# SpindlePidLcdStandAlone.net
KiCad netlist of a schematic drawn in EAGLE
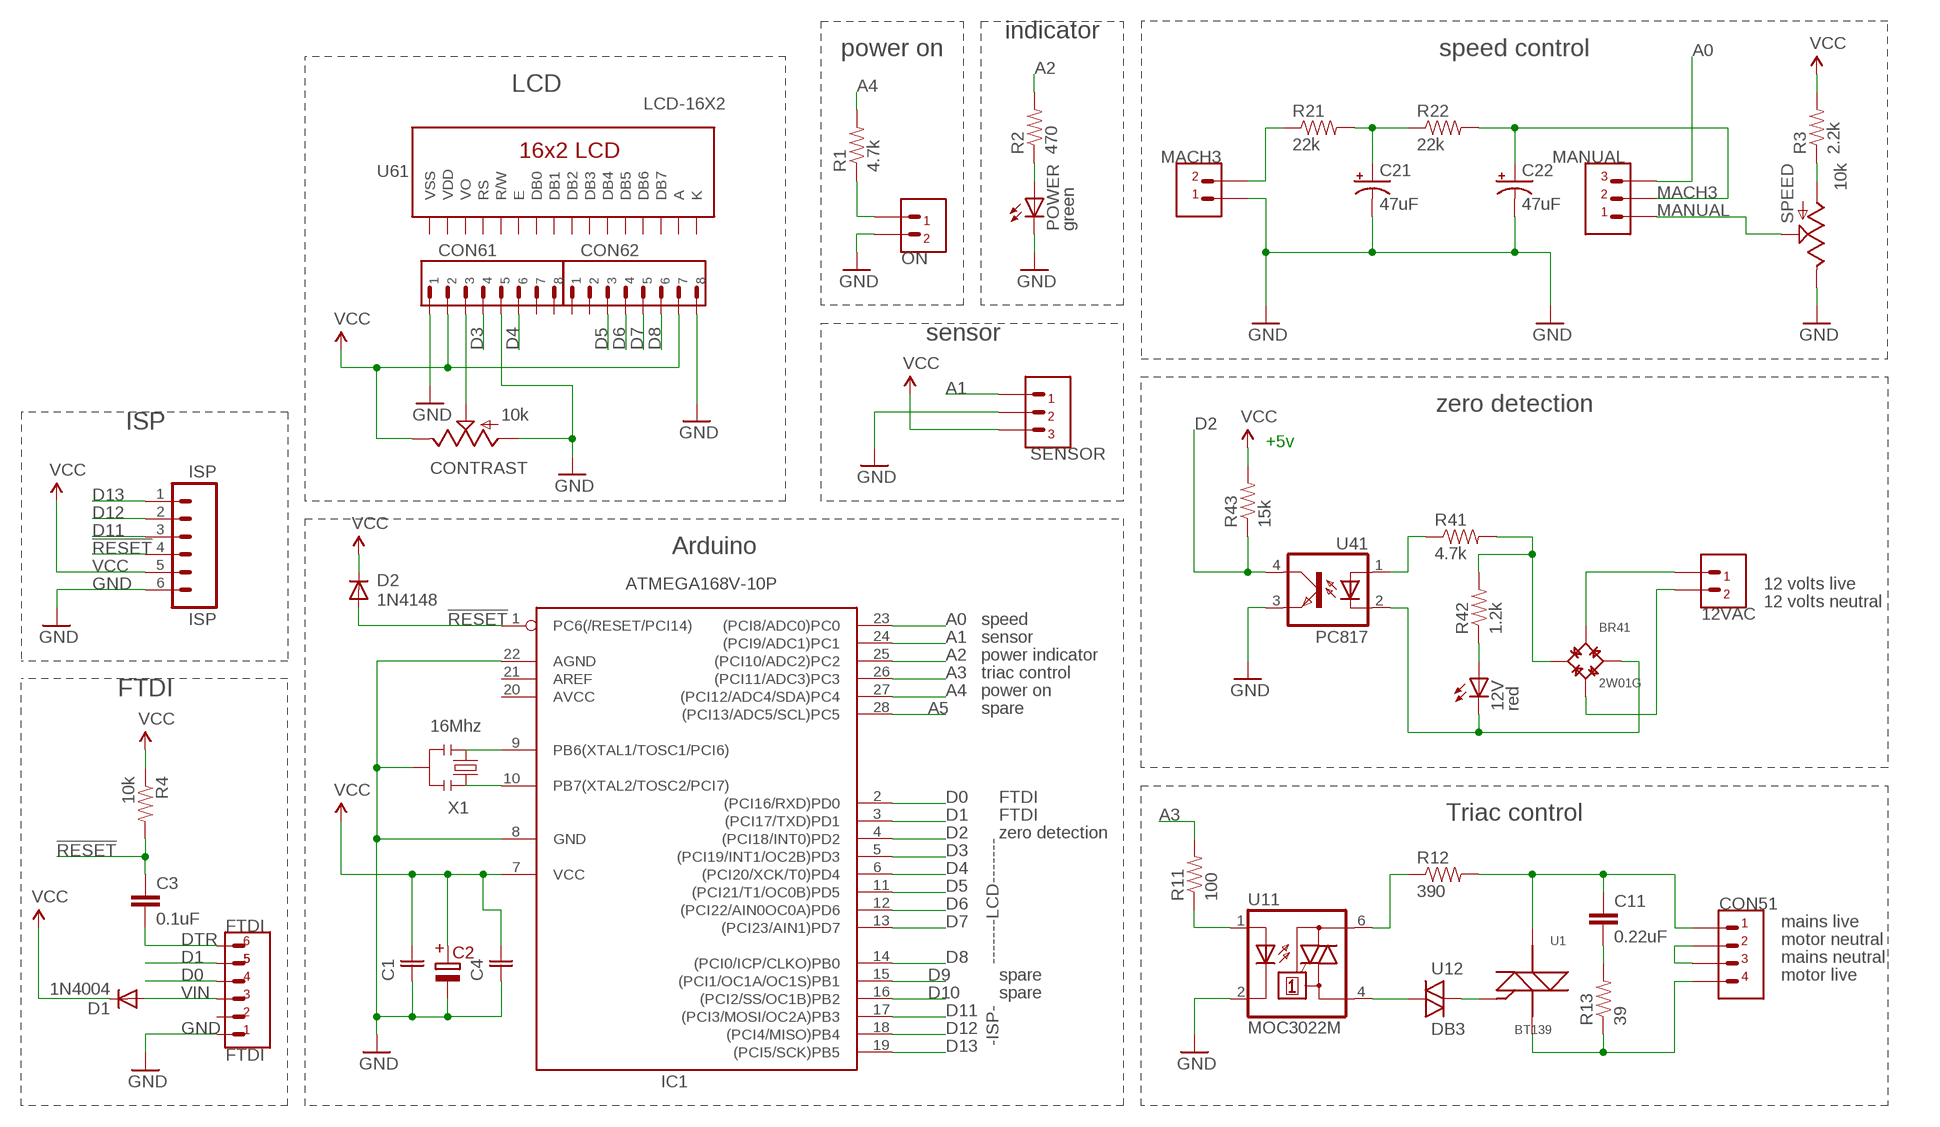
[diagram p0: schematic, sheet 1]

(export (version "E")
  (design (tool "Eeschema 10.0.6"))
  (components
    (comp (ref "12V")
      (value "red")
      (footprint "eagle-import:LED5MM")
      (libsource (lib "eagle-import") (part "LED5MM"))
    )
    (comp (ref "12VAC")
      (value "2PIN")
      (footprint "eagle-import:2PIN")
      (libsource (lib "eagle-import") (part "2PIN"))
    )
    (comp (ref "BR41")
      (value "2W01G")
      (footprint "eagle-import:DIODEBRIDGE")
      (libsource (lib "eagle-import") (part "DIODEBRIDGE"))
    )
    (comp (ref "C1")
      (value "0.1UF")
      (footprint "eagle-import:0.1UF")
      (libsource (lib "eagle-import") (part "0.1UF"))
    )
    (comp (ref "C2")
      (value "CAPACITOR")
      (footprint "eagle-import:CAPACITOR")
      (libsource (lib "eagle-import") (part "CAPACITOR"))
    )
    (comp (ref "C3")
      (value "0.1uF")
      (footprint "eagle-import:CAP-PTH-SMALL")
      (libsource (lib "eagle-import") (part "CAPPTH"))
    )
    (comp (ref "C4")
      (value "0.1UF")
      (footprint "eagle-import:0.1UF")
      (libsource (lib "eagle-import") (part "0.1UF"))
    )
    (comp (ref "C11")
      (value "0.22uF")
      (footprint "eagle-import:CAP-PTH-SMALL")
      (libsource (lib "eagle-import") (part "CAPPTH"))
    )
    (comp (ref "C21")
      (value "47uF")
      (footprint "eagle-import:CPOL-RADIAL-10UF-25V")
      (libsource (lib "eagle-import") (part "CAP_POLPTH2"))
    )
    (comp (ref "C22")
      (value "47uF")
      (footprint "eagle-import:CPOL-RADIAL-10UF-25V")
      (libsource (lib "eagle-import") (part "CAP_POLPTH2"))
    )
    (comp (ref "CON51")
      (value "4PIN")
      (footprint "eagle-import:4PIN")
      (libsource (lib "eagle-import") (part "4PIN"))
    )
    (comp (ref "CON61")
      (value "8PINHEADER")
      (footprint "eagle-import:8PINHEADER")
      (libsource (lib "eagle-import") (part "8PINHEADER"))
    )
    (comp (ref "CON62")
      (value "8PINHEADER")
      (footprint "eagle-import:8PINHEADER")
      (libsource (lib "eagle-import") (part "8PINHEADER"))
    )
    (comp (ref "CONTRAST")
      (value "10k")
      (footprint "eagle-import:ALPS_POT")
      (libsource (lib "eagle-import") (part "POT"))
    )
    (comp (ref "D1")
      (value "1N4004")
      (footprint "eagle-import:DO41-10")
      (libsource (lib "eagle-import") (part "1N4004"))
    )
    (comp (ref "D2")
      (value "1N4148")
      (footprint "eagle-import:DO41-10")
      (libsource (lib "eagle-import") (part "1N4004"))
    )
    (comp (ref "FTDI")
      (value "FTDI")
      (footprint "eagle-import:6PINHEADER")
      (libsource (lib "eagle-import") (part "6PINHEADER0.1{dblquote}"))
    )
    (comp (ref "IC1")
      (value "ATMEGA168V-10P")
      (footprint "eagle-import:DIL28-3")
      (libsource (lib "eagle-import") (part "ATMEGA168PV-10"))
    )
    (comp (ref "ISP")
      (value "ISP")
      (footprint "eagle-import:1X06")
      (libsource (lib "eagle-import") (part "M06SIP"))
    )
    (comp (ref "MACH3")
      (value "2PIN")
      (footprint "eagle-import:2PIN")
      (libsource (lib "eagle-import") (part "2PIN"))
    )
    (comp (ref "MANUAL")
      (value "3PIN")
      (footprint "eagle-import:3PIN")
      (libsource (lib "eagle-import") (part "3PIN"))
    )
    (comp (ref "ON")
      (value "2PIN")
      (footprint "eagle-import:2PIN")
      (libsource (lib "eagle-import") (part "2PIN"))
    )
    (comp (ref "POWER")
      (value "green")
      (footprint "eagle-import:LED5MM")
      (libsource (lib "eagle-import") (part "LED5MM"))
    )
    (comp (ref "R1")
      (value "4.7k")
      (footprint "eagle-import:AXIAL-0.4")
      (libsource (lib "eagle-import") (part "RESISTORPTH-1/4W"))
    )
    (comp (ref "R2")
      (value "470")
      (footprint "eagle-import:1_6W-RES")
      (libsource (lib "eagle-import") (part "RESISTORPTH-1/6W"))
    )
    (comp (ref "R3")
      (value "2.2k")
      (footprint "eagle-import:1_6W-RES")
      (libsource (lib "eagle-import") (part "RESISTORPTH-1/6W"))
    )
    (comp (ref "R4")
      (value "10k")
      (footprint "eagle-import:AXIAL-0.4")
      (libsource (lib "eagle-import") (part "RESISTORPTH-1/4W"))
    )
    (comp (ref "R11")
      (value "100")
      (footprint "eagle-import:1_6W-RES")
      (libsource (lib "eagle-import") (part "RESISTORPTH-1/6W"))
    )
    (comp (ref "R12")
      (value "390")
      (footprint "eagle-import:1_6W-RES")
      (libsource (lib "eagle-import") (part "RESISTORPTH-1/6W"))
    )
    (comp (ref "R13")
      (value "39")
      (footprint "eagle-import:1_6W-RES")
      (libsource (lib "eagle-import") (part "RESISTORPTH-1/6W"))
    )
    (comp (ref "R21")
      (value "22k")
      (footprint "eagle-import:1_6W-RES")
      (libsource (lib "eagle-import") (part "RESISTORPTH-1/6W"))
    )
    (comp (ref "R22")
      (value "22k")
      (footprint "eagle-import:1_6W-RES")
      (libsource (lib "eagle-import") (part "RESISTORPTH-1/6W"))
    )
    (comp (ref "R41")
      (value "4.7k")
      (footprint "eagle-import:1_6W-RES")
      (libsource (lib "eagle-import") (part "RESISTORPTH-1/6W"))
    )
    (comp (ref "R42")
      (value "1.2k")
      (footprint "eagle-import:1_6W-RES")
      (libsource (lib "eagle-import") (part "RESISTORPTH-1/6W"))
    )
    (comp (ref "R43")
      (value "15k")
      (footprint "eagle-import:1_6W-RES")
      (libsource (lib "eagle-import") (part "RESISTORPTH-1/6W"))
    )
    (comp (ref "SENSOR")
      (value "3PIN")
      (footprint "eagle-import:3PIN")
      (libsource (lib "eagle-import") (part "3PIN"))
    )
    (comp (ref "SPEED")
      (value "10k")
      (footprint "eagle-import:ALPS_POT")
      (libsource (lib "eagle-import") (part "POT"))
    )
    (comp (ref "U1")
      (value "BT139")
      (footprint "eagle-import:TRIAC")
      (libsource (lib "eagle-import") (part "TRIAC"))
    )
    (comp (ref "U11")
      (value "MOC3022M")
      (footprint "eagle-import:DIL06")
      (fields (field (name "MF") "FAIRCHILD SEMICONDUCTOR") (field (name "MPN") "MOC3022-M"))
      (libsource (lib "eagle-import") (part "MOC30M22"))
    )
    (comp (ref "U12")
      (value "DB3")
      (footprint "eagle-import:DO35-10")
      (libsource (lib "eagle-import") (part "DIAC-DO35-10"))
    )
    (comp (ref "U41")
      (value "PC817")
      (footprint "eagle-import:DIL04")
      (fields (field (name "MPN") "PC817X4J000F"))
      (libsource (lib "eagle-import") (part "PC817"))
    )
    (comp (ref "U61")
      (value "LCD-16X2")
      (footprint "eagle-import:LCD-16X2")
      (libsource (lib "eagle-import") (part "LCD-16X2SILK"))
    )
    (comp (ref "X1")
      (value "16Mhz")
      (footprint "eagle-import:RESONATOR-PTH")
      (libsource (lib "eagle-import") (part "RESONATORPTH"))
    )
  )
  (nets
    (net (code "1") (name "/A") (class "Default")
      (node (ref "U61") (pin "15") (pinfunction "A_15") (pintype "power_in"))
    )
    (net (code "2") (name "/A0") (class "Default")
      (node (ref "IC1") (pin "23") (pinfunction "(PCI8/ADC0)PC0_23") (pintype "bidirectional"))
      (node (ref "MANUAL") (pin "P$3") (pinfunction "3_P$3") (pintype "bidirectional"))
    )
    (net (code "3") (name "/A1") (class "Default")
      (node (ref "IC1") (pin "24") (pinfunction "(PCI9/ADC1)PC1_24") (pintype "bidirectional"))
      (node (ref "SENSOR") (pin "P$1") (pinfunction "1_P$1") (pintype "bidirectional"))
    )
    (net (code "4") (name "/A2") (class "Default")
      (node (ref "IC1") (pin "25") (pinfunction "(PCI10/ADC2)PC2_25") (pintype "bidirectional"))
      (node (ref "R2") (pin "2") (pinfunction "2_2") (pintype "passive"))
    )
    (net (code "5") (name "/A3") (class "Default")
      (node (ref "IC1") (pin "26") (pinfunction "(PCI11/ADC3)PC3_26") (pintype "bidirectional"))
      (node (ref "R11") (pin "2") (pinfunction "2_2") (pintype "passive"))
    )
    (net (code "6") (name "/A4") (class "Default")
      (node (ref "IC1") (pin "27") (pinfunction "(PCI12/ADC4/SDA)PC4_27") (pintype "bidirectional"))
      (node (ref "R1") (pin "P$2") (pinfunction "2_P$2") (pintype "passive"))
    )
    (net (code "7") (name "/A5") (class "Default")
      (node (ref "IC1") (pin "28") (pinfunction "(PCI13/ADC5/SCL)PC5_28") (pintype "bidirectional"))
    )
    (net (code "8") (name "/D0") (class "Default")
      (node (ref "FTDI") (pin "P$4") (pinfunction "P$4_P$4") (pintype "bidirectional"))
      (node (ref "IC1") (pin "2") (pinfunction "(PCI16/RXD)PD0_2") (pintype "bidirectional"))
    )
    (net (code "9") (name "/D1") (class "Default")
      (node (ref "FTDI") (pin "P$5") (pinfunction "P$5_P$5") (pintype "bidirectional"))
      (node (ref "IC1") (pin "3") (pinfunction "(PCI17/TXD)PD1_3") (pintype "bidirectional"))
    )
    (net (code "10") (name "/D2") (class "Default")
      (node (ref "IC1") (pin "4") (pinfunction "(PCI18/INT0)PD2_4") (pintype "bidirectional"))
      (node (ref "R43") (pin "1") (pinfunction "1_1") (pintype "passive"))
      (node (ref "U41") (pin "4") (pinfunction "COL_4") (pintype "passive"))
    )
    (net (code "11") (name "/D3") (class "Default")
      (node (ref "CON61") (pin "P$4") (pinfunction "P$4_P$4") (pintype "bidirectional"))
      (node (ref "IC1") (pin "5") (pinfunction "(PCI19/INT1/OC2B)PD3_5") (pintype "bidirectional"))
    )
    (net (code "12") (name "/D4") (class "Default")
      (node (ref "CON61") (pin "P$6") (pinfunction "P$6_P$6") (pintype "bidirectional"))
      (node (ref "IC1") (pin "6") (pinfunction "(PCI20/XCK/T0)PD4_6") (pintype "bidirectional"))
    )
    (net (code "13") (name "/D5") (class "Default")
      (node (ref "CON62") (pin "P$3") (pinfunction "P$3_P$3") (pintype "bidirectional"))
      (node (ref "IC1") (pin "11") (pinfunction "(PCI21/T1/OC0B)PD5_11") (pintype "bidirectional"))
    )
    (net (code "14") (name "/D6") (class "Default")
      (node (ref "CON62") (pin "P$4") (pinfunction "P$4_P$4") (pintype "bidirectional"))
      (node (ref "IC1") (pin "12") (pinfunction "(PCI22/AIN0OC0A)PD6_12") (pintype "bidirectional"))
    )
    (net (code "15") (name "/D7") (class "Default")
      (node (ref "CON62") (pin "P$5") (pinfunction "P$5_P$5") (pintype "bidirectional"))
      (node (ref "IC1") (pin "13") (pinfunction "(PCI23/AIN1)PD7_13") (pintype "bidirectional"))
    )
    (net (code "16") (name "/D8") (class "Default")
      (node (ref "CON62") (pin "P$6") (pinfunction "P$6_P$6") (pintype "bidirectional"))
      (node (ref "IC1") (pin "14") (pinfunction "(PCI0/ICP/CLKO)PB0_14") (pintype "bidirectional"))
    )
    (net (code "17") (name "/D9") (class "Default")
      (node (ref "IC1") (pin "15") (pinfunction "(PCI1/OC1A/OC1S)PB1_15") (pintype "bidirectional"))
    )
    (net (code "18") (name "/D10") (class "Default")
      (node (ref "IC1") (pin "16") (pinfunction "(PCI2/SS/OC1B)PB2_16") (pintype "bidirectional"))
    )
    (net (code "19") (name "/D11") (class "Default")
      (node (ref "IC1") (pin "17") (pinfunction "(PCI3/MOSI/OC2A)PB3_17") (pintype "bidirectional"))
      (node (ref "ISP") (pin "3") (pinfunction "3_3") (pintype "passive"))
    )
    (net (code "20") (name "/D12") (class "Default")
      (node (ref "IC1") (pin "18") (pinfunction "(PCI4/MISO)PB4_18") (pintype "bidirectional"))
      (node (ref "ISP") (pin "2") (pinfunction "2_2") (pintype "passive"))
    )
    (net (code "21") (name "/D13") (class "Default")
      (node (ref "IC1") (pin "19") (pinfunction "(PCI5/SCK)PB5_19") (pintype "bidirectional"))
      (node (ref "ISP") (pin "1") (pinfunction "1_1") (pintype "passive"))
    )
    (net (code "22") (name "/DTR") (class "Default")
      (node (ref "C3") (pin "2") (pinfunction "2_2") (pintype "passive"))
      (node (ref "FTDI") (pin "P$6") (pinfunction "P$6_P$6") (pintype "bidirectional"))
    )
    (net (code "23") (name "/K") (class "Default")
      (node (ref "U61") (pin "16") (pinfunction "K_16") (pintype "power_in"))
    )
    (net (code "24") (name "/MACH3") (class "Default")
      (node (ref "C22") (pin "1") (pinfunction "+_1") (pintype "passive"))
      (node (ref "MANUAL") (pin "P$2") (pinfunction "2_P$2") (pintype "bidirectional"))
      (node (ref "R22") (pin "2") (pinfunction "2_2") (pintype "passive"))
    )
    (net (code "25") (name "/MANUAL") (class "Default")
      (node (ref "MANUAL") (pin "P$1") (pinfunction "1_P$1") (pintype "bidirectional"))
      (node (ref "SPEED") (pin "P$2") (pinfunction "S_P$2") (pintype "passive"))
    )
    (net (code "26") (name "/VDD") (class "Default")
      (node (ref "U61") (pin "2") (pinfunction "VDD_2") (pintype "power_in"))
    )
    (net (code "27") (name "/VIN") (class "Default")
      (node (ref "D1") (pin "A") (pinfunction "A_A") (pintype "passive"))
      (node (ref "FTDI") (pin "P$3") (pinfunction "P$3_P$3") (pintype "bidirectional"))
    )
    (net (code "28") (name "/VSS") (class "Default")
      (node (ref "U61") (pin "1") (pinfunction "VSS_1") (pintype "power_in"))
    )
    (net (code "29") (name "/~{RESET}") (class "Default")
      (node (ref "C3") (pin "1") (pinfunction "1_1") (pintype "passive"))
      (node (ref "D2") (pin "A") (pinfunction "A_A") (pintype "passive"))
      (node (ref "IC1") (pin "1") (pinfunction "PC6(/RESET/PCI14)_1") (pintype "bidirectional"))
      (node (ref "ISP") (pin "4") (pinfunction "4_4") (pintype "passive"))
      (node (ref "R4") (pin "P$2") (pinfunction "2_P$2") (pintype "passive"))
    )
    (net (code "30") (name "GND") (class "Default")
      (node (ref "C1") (pin "P$1") (pinfunction "P$1_P$1") (pintype "bidirectional"))
      (node (ref "C2") (pin "-") (pinfunction "-VE_-") (pintype "bidirectional"))
      (node (ref "C21") (pin "2") (pinfunction "-_2") (pintype "passive"))
      (node (ref "C22") (pin "2") (pinfunction "-_2") (pintype "passive"))
      (node (ref "C4") (pin "P$1") (pinfunction "P$1_P$1") (pintype "bidirectional"))
      (node (ref "CON61") (pin "P$1") (pinfunction "P$1_P$1") (pintype "bidirectional"))
      (node (ref "CON61") (pin "P$5") (pinfunction "P$5_P$5") (pintype "bidirectional"))
      (node (ref "CON62") (pin "P$8") (pinfunction "P$8_P$8") (pintype "bidirectional"))
      (node (ref "CONTRAST") (pin "P$3") (pinfunction "A_P$3") (pintype "passive"))
      (node (ref "FTDI") (pin "P$1") (pinfunction "P$1_P$1") (pintype "bidirectional"))
      (node (ref "IC1") (pin "22") (pinfunction "AGND_22") (pintype "bidirectional"))
      (node (ref "IC1") (pin "8") (pinfunction "GND_8") (pintype "bidirectional"))
      (node (ref "ISP") (pin "6") (pinfunction "6_6") (pintype "passive"))
      (node (ref "MACH3") (pin "P$1") (pinfunction "P$1_P$1") (pintype "bidirectional"))
      (node (ref "ON") (pin "P$2") (pinfunction "P$2_P$2") (pintype "bidirectional"))
      (node (ref "POWER") (pin "K") (pinfunction "C_K") (pintype "passive"))
      (node (ref "SENSOR") (pin "P$2") (pinfunction "2_P$2") (pintype "bidirectional"))
      (node (ref "SPEED") (pin "P$1") (pinfunction "E_P$1") (pintype "passive"))
      (node (ref "U11") (pin "2") (pinfunction "C_2") (pintype "passive"))
      (node (ref "U41") (pin "3") (pinfunction "EMIT_3") (pintype "passive"))
      (node (ref "X1") (pin "2") (pinfunction "2_2") (pintype "passive"))
    )
    (net (code "31") (name "Net-(12V-C)") (class "Default")
      (node (ref "12V") (pin "K") (pinfunction "C_K") (pintype "passive"))
      (node (ref "BR41") (pin "-") (pinfunction "-_-") (pintype "bidirectional"))
      (node (ref "U41") (pin "2") (pinfunction "C_2") (pintype "passive"))
    )
    (net (code "32") (name "Net-(12V-PadA)") (class "Default")
      (node (ref "12V") (pin "A") (pinfunction "A_A") (pintype "passive"))
      (node (ref "R42") (pin "1") (pinfunction "1_1") (pintype "passive"))
    )
    (net (code "33") (name "Net-(12VAC-PadP$1)") (class "Default")
      (node (ref "12VAC") (pin "P$1") (pinfunction "P$1_P$1") (pintype "bidirectional"))
      (node (ref "BR41") (pin "AC1") (pinfunction "AC1_AC1") (pintype "bidirectional"))
    )
    (net (code "34") (name "Net-(12VAC-PadP$2)") (class "Default")
      (node (ref "12VAC") (pin "P$2") (pinfunction "P$2_P$2") (pintype "bidirectional"))
      (node (ref "BR41") (pin "AC2") (pinfunction "AC2_AC2") (pintype "bidirectional"))
    )
    (net (code "35") (name "Net-(BR41-Pad+)") (class "Default")
      (node (ref "BR41") (pin "+") (pinfunction "+_+") (pintype "bidirectional"))
      (node (ref "R41") (pin "2") (pinfunction "2_2") (pintype "passive"))
      (node (ref "R42") (pin "2") (pinfunction "2_2") (pintype "passive"))
    )
    (net (code "36") (name "Net-(C11-Pad2)") (class "Default")
      (node (ref "C11") (pin "2") (pinfunction "2_2") (pintype "passive"))
      (node (ref "R13") (pin "2") (pinfunction "2_2") (pintype "passive"))
    )
    (net (code "37") (name "Net-(C21-+)") (class "Default")
      (node (ref "C21") (pin "1") (pinfunction "+_1") (pintype "passive"))
      (node (ref "R21") (pin "2") (pinfunction "2_2") (pintype "passive"))
      (node (ref "R22") (pin "1") (pinfunction "1_1") (pintype "passive"))
    )
    (net (code "38") (name "Net-(CON51-PadP$2)") (class "Default")
      (node (ref "CON51") (pin "P$2") (pinfunction "P$2_P$2") (pintype "bidirectional"))
      (node (ref "CON51") (pin "P$3") (pinfunction "P$3_P$3") (pintype "bidirectional"))
    )
    (net (code "39") (name "Net-(CONTRAST-S)") (class "Default")
      (node (ref "CON61") (pin "P$3") (pinfunction "P$3_P$3") (pintype "bidirectional"))
      (node (ref "CONTRAST") (pin "P$2") (pinfunction "S_P$2") (pintype "passive"))
    )
    (net (code "40") (name "Net-(IC1-PB6(XTAL1{slash}TOSC1{slash}PCI6))") (class "Default")
      (node (ref "IC1") (pin "9") (pinfunction "PB6(XTAL1/TOSC1/PCI6)_9") (pintype "bidirectional"))
      (node (ref "X1") (pin "1") (pinfunction "1_1") (pintype "passive"))
    )
    (net (code "41") (name "Net-(IC1-PB7(XTAL2{slash}TOSC2{slash}PCI7))") (class "Default")
      (node (ref "IC1") (pin "10") (pinfunction "PB7(XTAL2/TOSC2/PCI7)_10") (pintype "bidirectional"))
      (node (ref "X1") (pin "3") (pinfunction "3_3") (pintype "passive"))
    )
    (net (code "42") (name "Net-(MACH3-PadP$2)") (class "Default")
      (node (ref "MACH3") (pin "P$2") (pinfunction "P$2_P$2") (pintype "bidirectional"))
      (node (ref "R21") (pin "1") (pinfunction "1_1") (pintype "passive"))
    )
    (net (code "43") (name "Net-(POWER-PadA)") (class "Default")
      (node (ref "POWER") (pin "A") (pinfunction "A_A") (pintype "passive"))
      (node (ref "R2") (pin "1") (pinfunction "1_1") (pintype "passive"))
    )
    (net (code "44") (name "Net-(R1-1)") (class "Default")
      (node (ref "ON") (pin "P$1") (pinfunction "P$1_P$1") (pintype "bidirectional"))
      (node (ref "R1") (pin "P$1") (pinfunction "1_P$1") (pintype "passive"))
    )
    (net (code "45") (name "Net-(SPEED-A)") (class "Default")
      (node (ref "R3") (pin "1") (pinfunction "1_1") (pintype "passive"))
      (node (ref "SPEED") (pin "P$3") (pinfunction "A_P$3") (pintype "passive"))
    )
    (net (code "46") (name "Net-(U1-A)") (class "Default")
      (node (ref "C11") (pin "1") (pinfunction "1_1") (pintype "passive"))
      (node (ref "CON51") (pin "P$1") (pinfunction "P$1_P$1") (pintype "bidirectional"))
      (node (ref "R12") (pin "2") (pinfunction "2_2") (pintype "passive"))
      (node (ref "U1") (pin "2") (pinfunction "A_2") (pintype "bidirectional"))
    )
    (net (code "47") (name "Net-(U1-B)") (class "Default")
      (node (ref "U1") (pin "1") (pinfunction "B_1") (pintype "bidirectional"))
      (node (ref "U12") (pin "C") (pinfunction "2_C") (pintype "passive"))
    )
    (net (code "48") (name "Net-(U1-C)") (class "Default")
      (node (ref "CON51") (pin "P$4") (pinfunction "P$4_P$4") (pintype "bidirectional"))
      (node (ref "R13") (pin "1") (pinfunction "1_1") (pintype "passive"))
      (node (ref "U1") (pin "3") (pinfunction "C_3") (pintype "bidirectional"))
    )
    (net (code "49") (name "Net-(U11-A)") (class "Default")
      (node (ref "R11") (pin "1") (pinfunction "1_1") (pintype "passive"))
      (node (ref "U11") (pin "1") (pinfunction "A_1") (pintype "passive"))
    )
    (net (code "50") (name "Net-(U11-A1)") (class "Default")
      (node (ref "U11") (pin "4") (pinfunction "A1_4") (pintype "passive"))
      (node (ref "U12") (pin "A") (pinfunction "1_A") (pintype "passive"))
    )
    (net (code "51") (name "Net-(U11-A2)") (class "Default")
      (node (ref "R12") (pin "1") (pinfunction "1_1") (pintype "passive"))
      (node (ref "U11") (pin "6") (pinfunction "A2_6") (pintype "passive"))
    )
    (net (code "52") (name "Net-(U41-A)") (class "Default")
      (node (ref "R41") (pin "1") (pinfunction "1_1") (pintype "passive"))
      (node (ref "U41") (pin "1") (pinfunction "A_1") (pintype "passive"))
    )
    (net (code "53") (name "VCC") (class "Default")
      (node (ref "C1") (pin "P$2") (pinfunction "P$2_P$2") (pintype "bidirectional"))
      (node (ref "C2") (pin "+") (pinfunction "+VE_+") (pintype "bidirectional"))
      (node (ref "C4") (pin "P$2") (pinfunction "P$2_P$2") (pintype "bidirectional"))
      (node (ref "CON61") (pin "P$2") (pinfunction "P$2_P$2") (pintype "bidirectional"))
      (node (ref "CON62") (pin "P$7") (pinfunction "P$7_P$7") (pintype "bidirectional"))
      (node (ref "CONTRAST") (pin "P$1") (pinfunction "E_P$1") (pintype "passive"))
      (node (ref "D1") (pin "C") (pinfunction "C_C") (pintype "passive"))
      (node (ref "D2") (pin "C") (pinfunction "C_C") (pintype "passive"))
      (node (ref "IC1") (pin "7") (pinfunction "VCC_7") (pintype "bidirectional"))
      (node (ref "ISP") (pin "5") (pinfunction "5_5") (pintype "passive"))
      (node (ref "R3") (pin "2") (pinfunction "2_2") (pintype "passive"))
      (node (ref "R4") (pin "P$1") (pinfunction "1_P$1") (pintype "passive"))
      (node (ref "R43") (pin "2") (pinfunction "2_2") (pintype "passive"))
      (node (ref "SENSOR") (pin "P$3") (pinfunction "3_P$3") (pintype "bidirectional"))
    )
    (net (code "54") (name "unconnected-(CON61-PadP$7)") (class "Default")
      (node (ref "CON61") (pin "P$7") (pinfunction "P$7_P$7") (pintype "bidirectional"))
    )
    (net (code "55") (name "unconnected-(CON61-PadP$8)") (class "Default")
      (node (ref "CON61") (pin "P$8") (pinfunction "P$8_P$8") (pintype "bidirectional"))
    )
    (net (code "56") (name "unconnected-(CON62-PadP$1)") (class "Default")
      (node (ref "CON62") (pin "P$1") (pinfunction "P$1_P$1") (pintype "bidirectional"))
    )
    (net (code "57") (name "unconnected-(CON62-PadP$2)") (class "Default")
      (node (ref "CON62") (pin "P$2") (pinfunction "P$2_P$2") (pintype "bidirectional"))
    )
    (net (code "58") (name "unconnected-(FTDI-PadP$2)") (class "Default")
      (node (ref "FTDI") (pin "P$2") (pinfunction "P$2_P$2") (pintype "bidirectional"))
    )
    (net (code "59") (name "unconnected-(IC1-AREF-Pad21)") (class "Default")
      (node (ref "IC1") (pin "21") (pinfunction "AREF_21") (pintype "bidirectional"))
    )
    (net (code "60") (name "unconnected-(IC1-AVCC-Pad20)") (class "Default")
      (node (ref "IC1") (pin "20") (pinfunction "AVCC_20") (pintype "bidirectional"))
    )
    (net (code "61") (name "unconnected-(U61-DB0-Pad7)") (class "Default")
      (node (ref "U61") (pin "7") (pinfunction "DB0_7") (pintype "bidirectional"))
    )
    (net (code "62") (name "unconnected-(U61-DB1-Pad8)") (class "Default")
      (node (ref "U61") (pin "8") (pinfunction "DB1_8") (pintype "bidirectional"))
    )
    (net (code "63") (name "unconnected-(U61-DB2-Pad9)") (class "Default")
      (node (ref "U61") (pin "9") (pinfunction "DB2_9") (pintype "bidirectional"))
    )
    (net (code "64") (name "unconnected-(U61-DB3-Pad10)") (class "Default")
      (node (ref "U61") (pin "10") (pinfunction "DB3_10") (pintype "bidirectional"))
    )
    (net (code "65") (name "unconnected-(U61-DB4-Pad11)") (class "Default")
      (node (ref "U61") (pin "11") (pinfunction "DB4_11") (pintype "bidirectional"))
    )
    (net (code "66") (name "unconnected-(U61-DB5-Pad12)") (class "Default")
      (node (ref "U61") (pin "12") (pinfunction "DB5_12") (pintype "bidirectional"))
    )
    (net (code "67") (name "unconnected-(U61-DB6-Pad13)") (class "Default")
      (node (ref "U61") (pin "13") (pinfunction "DB6_13") (pintype "bidirectional"))
    )
    (net (code "68") (name "unconnected-(U61-DB7-Pad14)") (class "Default")
      (node (ref "U61") (pin "14") (pinfunction "DB7_14") (pintype "bidirectional"))
    )
    (net (code "69") (name "unconnected-(U61-E-Pad6)") (class "Default")
      (node (ref "U61") (pin "6") (pinfunction "E_6") (pintype "input"))
    )
    (net (code "70") (name "unconnected-(U61-RS-Pad4)") (class "Default")
      (node (ref "U61") (pin "4") (pinfunction "RS_4") (pintype "input"))
    )
    (net (code "71") (name "unconnected-(U61-R{slash}W-Pad5)") (class "Default")
      (node (ref "U61") (pin "5") (pinfunction "R/W_5") (pintype "input"))
    )
    (net (code "72") (name "unconnected-(U61-VO-Pad3)") (class "Default")
      (node (ref "U61") (pin "3") (pinfunction "VO_3") (pintype "bidirectional"))
    )
  )
)
